# cartridge_pcb.net
KiCad netlist of a schematic drawn in EAGLE
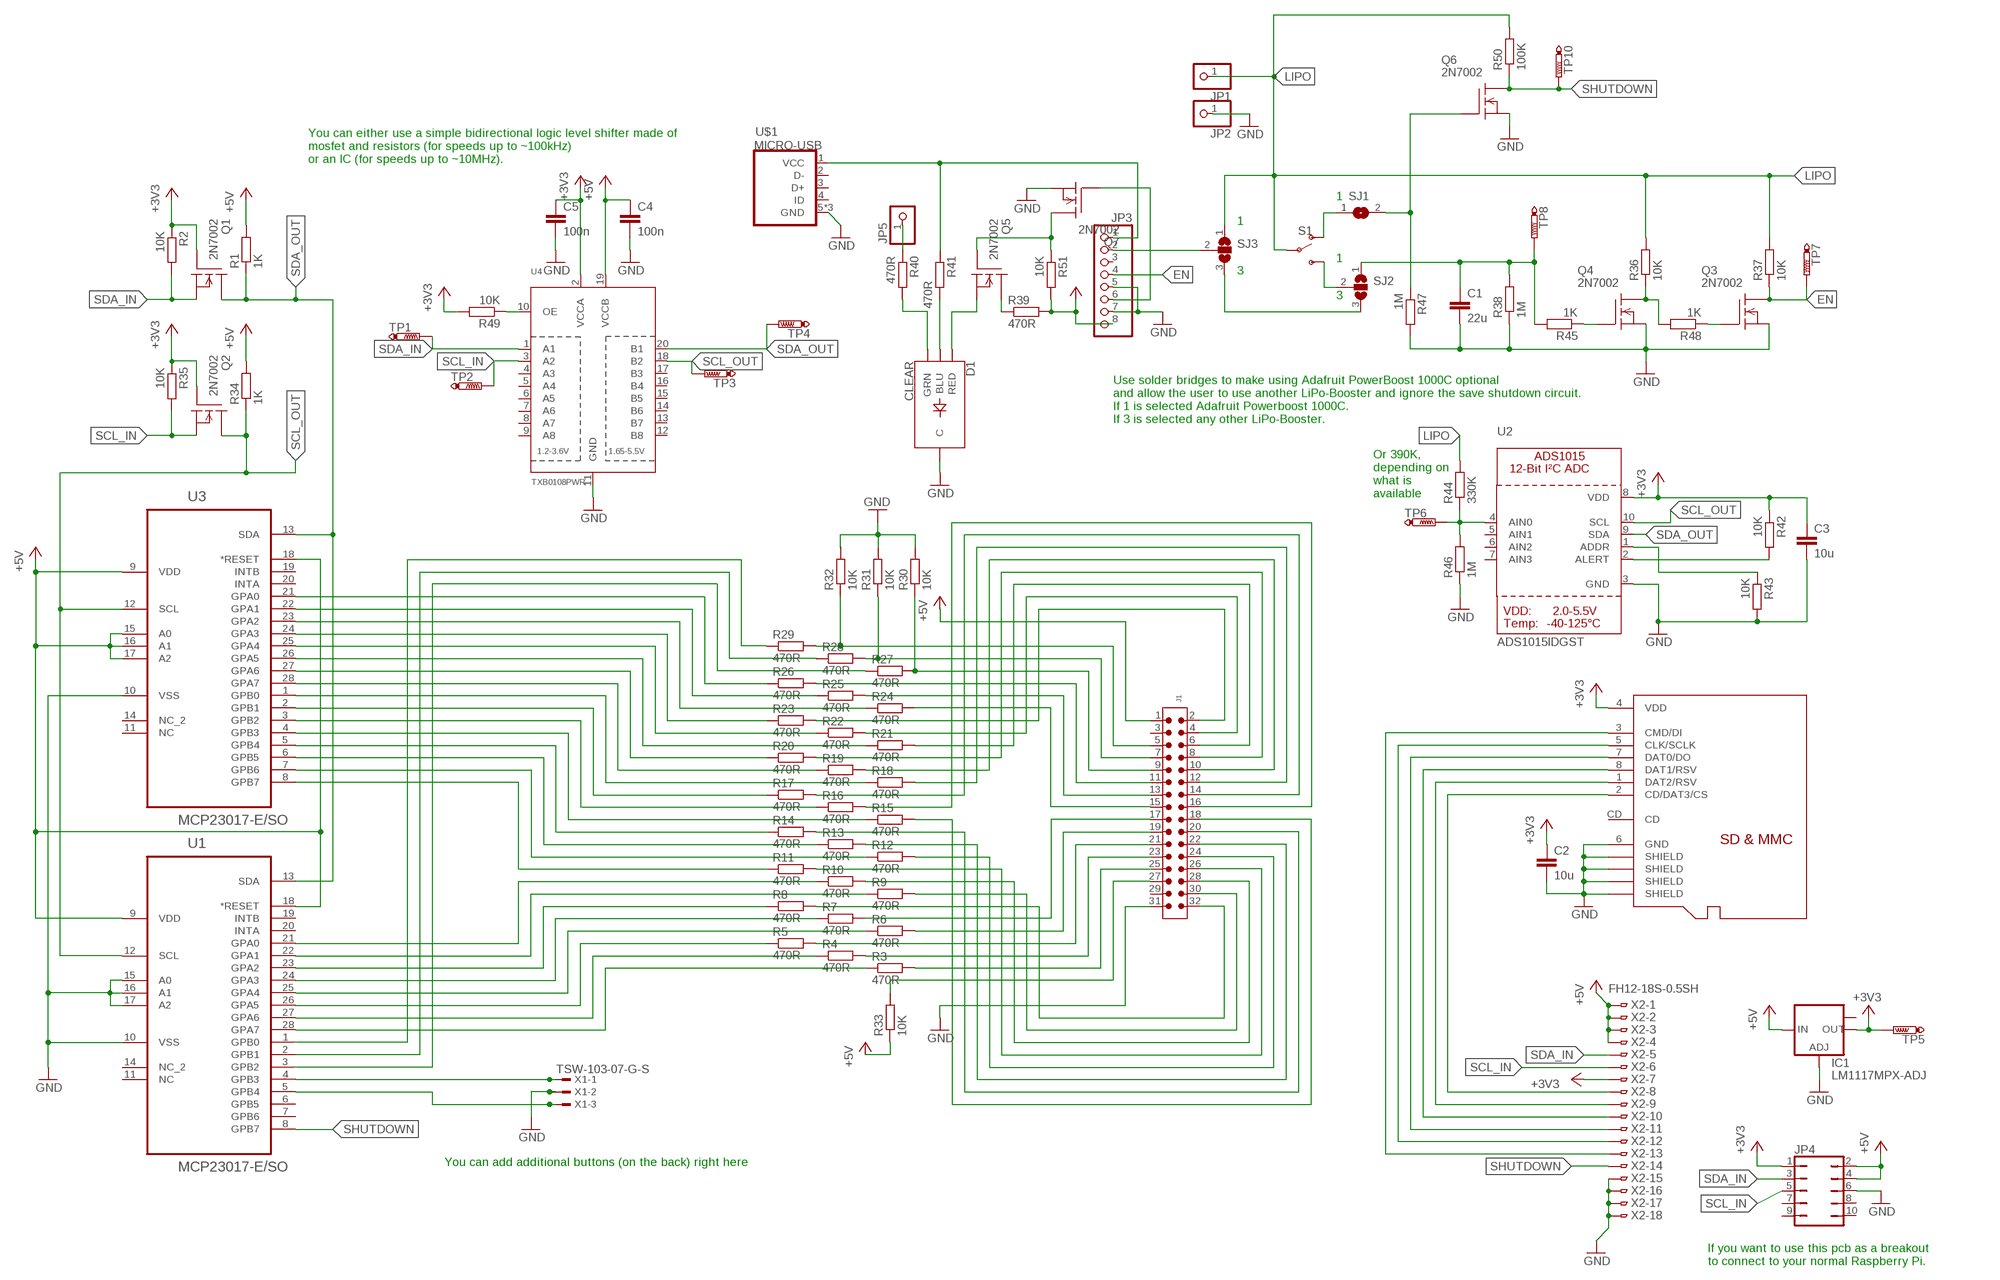
[diagram p0: schematic, sheet 1]

(export (version "E")
  (design (tool "Eeschema 10.0.6"))
  (components
    (comp (ref "C1")
      (value "22u")
      (footprint "eagle-import:C0805")
      (libsource (lib "eagle-import") (part "C-EUC0805"))
    )
    (comp (ref "C2")
      (value "10u")
      (footprint "eagle-import:C0805")
      (libsource (lib "eagle-import") (part "C-EUC0805"))
    )
    (comp (ref "C3")
      (value "10u")
      (footprint "eagle-import:C0805")
      (libsource (lib "eagle-import") (part "C-EUC0805"))
    )
    (comp (ref "C4")
      (value "100n")
      (footprint "eagle-import:C0805")
      (libsource (lib "eagle-import") (part "C-EUC0805"))
    )
    (comp (ref "C5")
      (value "100n")
      (footprint "eagle-import:C0805")
      (libsource (lib "eagle-import") (part "C-EUC0805"))
    )
    (comp (ref "D1")
      (value "CLEAR")
      (footprint "eagle-import:LED-RGB-THRU")
      (libsource (lib "eagle-import") (part "LED-RGB-CCCLEAR"))
    )
    (comp (ref "IC1")
      (value "LM1117MPX-ADJ")
      (footprint "eagle-import:SOT223")
      (libsource (lib "eagle-import") (part "LM1117MPX-ADJ"))
    )
    (comp (ref "J1")
      (value "6130XX21121_61303221121")
      (footprint "eagle-import:61303221121")
      (libsource (lib "eagle-import") (part "6130XX21121_61303221121"))
    )
    (comp (ref "JP1")
      (value "PINHD-1X1")
      (footprint "eagle-import:1X01")
      (libsource (lib "eagle-import") (part "PINHD-1X1"))
    )
    (comp (ref "JP2")
      (value "PINHD-1X1")
      (footprint "eagle-import:1X01")
      (libsource (lib "eagle-import") (part "PINHD-1X1"))
    )
    (comp (ref "JP3")
      (value "HEADER-1X8ROUND")
      (footprint "eagle-import:1X08_ROUND")
      (libsource (lib "eagle-import") (part "HEADER-1X8ROUND"))
    )
    (comp (ref "JP4")
      (value "JP5Q")
      (footprint "eagle-import:JP5Q")
      (libsource (lib "eagle-import") (part "JP5Q"))
    )
    (comp (ref "JP5")
      (value "PINHD-1X1")
      (footprint "eagle-import:1X01")
      (libsource (lib "eagle-import") (part "PINHD-1X1"))
    )
    (comp (ref "Q1")
      (value "2N7002")
      (footprint "eagle-import:SOT23")
      (libsource (lib "eagle-import") (part "2N7002"))
    )
    (comp (ref "Q2")
      (value "2N7002")
      (footprint "eagle-import:SOT23")
      (libsource (lib "eagle-import") (part "2N7002"))
    )
    (comp (ref "Q3")
      (value "2N7002")
      (footprint "eagle-import:SOT23")
      (libsource (lib "eagle-import") (part "2N7002"))
    )
    (comp (ref "Q4")
      (value "2N7002")
      (footprint "eagle-import:SOT23")
      (libsource (lib "eagle-import") (part "2N7002"))
    )
    (comp (ref "Q5")
      (value "2N7002")
      (footprint "eagle-import:SOT23")
      (libsource (lib "eagle-import") (part "2N7002"))
    )
    (comp (ref "Q6")
      (value "2N7002")
      (footprint "eagle-import:SOT23")
      (libsource (lib "eagle-import") (part "2N7002"))
    )
    (comp (ref "Q7")
      (value "2N7002")
      (footprint "eagle-import:SOT23")
      (libsource (lib "eagle-import") (part "2N7002"))
    )
    (comp (ref "R1")
      (value "1K")
      (footprint "eagle-import:R0805")
      (libsource (lib "eagle-import") (part "R-EU_R0805"))
    )
    (comp (ref "R2")
      (value "10K")
      (footprint "eagle-import:R0805")
      (libsource (lib "eagle-import") (part "R-EU_R0805"))
    )
    (comp (ref "R3")
      (value "470R")
      (footprint "eagle-import:R0805")
      (libsource (lib "eagle-import") (part "R-EU_R0805"))
    )
    (comp (ref "R4")
      (value "470R")
      (footprint "eagle-import:R0805")
      (libsource (lib "eagle-import") (part "R-EU_R0805"))
    )
    (comp (ref "R5")
      (value "470R")
      (footprint "eagle-import:R0805")
      (libsource (lib "eagle-import") (part "R-EU_R0805"))
    )
    (comp (ref "R6")
      (value "470R")
      (footprint "eagle-import:R0805")
      (libsource (lib "eagle-import") (part "R-EU_R0805"))
    )
    (comp (ref "R7")
      (value "470R")
      (footprint "eagle-import:R0805")
      (libsource (lib "eagle-import") (part "R-EU_R0805"))
    )
    (comp (ref "R8")
      (value "470R")
      (footprint "eagle-import:R0805")
      (libsource (lib "eagle-import") (part "R-EU_R0805"))
    )
    (comp (ref "R9")
      (value "470R")
      (footprint "eagle-import:R0805")
      (libsource (lib "eagle-import") (part "R-EU_R0805"))
    )
    (comp (ref "R10")
      (value "470R")
      (footprint "eagle-import:R0805")
      (libsource (lib "eagle-import") (part "R-EU_R0805"))
    )
    (comp (ref "R11")
      (value "470R")
      (footprint "eagle-import:R0805")
      (libsource (lib "eagle-import") (part "R-EU_R0805"))
    )
    (comp (ref "R12")
      (value "470R")
      (footprint "eagle-import:R0805")
      (libsource (lib "eagle-import") (part "R-EU_R0805"))
    )
    (comp (ref "R13")
      (value "470R")
      (footprint "eagle-import:R0805")
      (libsource (lib "eagle-import") (part "R-EU_R0805"))
    )
    (comp (ref "R14")
      (value "470R")
      (footprint "eagle-import:R0805")
      (libsource (lib "eagle-import") (part "R-EU_R0805"))
    )
    (comp (ref "R15")
      (value "470R")
      (footprint "eagle-import:R0805")
      (libsource (lib "eagle-import") (part "R-EU_R0805"))
    )
    (comp (ref "R16")
      (value "470R")
      (footprint "eagle-import:R0805")
      (libsource (lib "eagle-import") (part "R-EU_R0805"))
    )
    (comp (ref "R17")
      (value "470R")
      (footprint "eagle-import:R0805")
      (libsource (lib "eagle-import") (part "R-EU_R0805"))
    )
    (comp (ref "R18")
      (value "470R")
      (footprint "eagle-import:R0805")
      (libsource (lib "eagle-import") (part "R-EU_R0805"))
    )
    (comp (ref "R19")
      (value "470R")
      (footprint "eagle-import:R0805")
      (libsource (lib "eagle-import") (part "R-EU_R0805"))
    )
    (comp (ref "R20")
      (value "470R")
      (footprint "eagle-import:R0805")
      (libsource (lib "eagle-import") (part "R-EU_R0805"))
    )
    (comp (ref "R21")
      (value "470R")
      (footprint "eagle-import:R0805")
      (libsource (lib "eagle-import") (part "R-EU_R0805"))
    )
    (comp (ref "R22")
      (value "470R")
      (footprint "eagle-import:R0805")
      (libsource (lib "eagle-import") (part "R-EU_R0805"))
    )
    (comp (ref "R23")
      (value "470R")
      (footprint "eagle-import:R0805")
      (libsource (lib "eagle-import") (part "R-EU_R0805"))
    )
    (comp (ref "R24")
      (value "470R")
      (footprint "eagle-import:R0805")
      (libsource (lib "eagle-import") (part "R-EU_R0805"))
    )
    (comp (ref "R25")
      (value "470R")
      (footprint "eagle-import:R0805")
      (libsource (lib "eagle-import") (part "R-EU_R0805"))
    )
    (comp (ref "R26")
      (value "470R")
      (footprint "eagle-import:R0805")
      (libsource (lib "eagle-import") (part "R-EU_R0805"))
    )
    (comp (ref "R27")
      (value "470R")
      (footprint "eagle-import:R0805")
      (libsource (lib "eagle-import") (part "R-EU_R0805"))
    )
    (comp (ref "R28")
      (value "470R")
      (footprint "eagle-import:R0805")
      (libsource (lib "eagle-import") (part "R-EU_R0805"))
    )
    (comp (ref "R29")
      (value "470R")
      (footprint "eagle-import:R0805")
      (libsource (lib "eagle-import") (part "R-EU_R0805"))
    )
    (comp (ref "R30")
      (value "10K")
      (footprint "eagle-import:R0805")
      (libsource (lib "eagle-import") (part "R-EU_R0805"))
    )
    (comp (ref "R31")
      (value "10K")
      (footprint "eagle-import:R0805")
      (libsource (lib "eagle-import") (part "R-EU_R0805"))
    )
    (comp (ref "R32")
      (value "10K")
      (footprint "eagle-import:R0805")
      (libsource (lib "eagle-import") (part "R-EU_R0805"))
    )
    (comp (ref "R33")
      (value "10K")
      (footprint "eagle-import:R0805")
      (libsource (lib "eagle-import") (part "R-EU_R0805"))
    )
    (comp (ref "R34")
      (value "1K")
      (footprint "eagle-import:R0805")
      (libsource (lib "eagle-import") (part "R-EU_R0805"))
    )
    (comp (ref "R35")
      (value "10K")
      (footprint "eagle-import:R0805")
      (libsource (lib "eagle-import") (part "R-EU_R0805"))
    )
    (comp (ref "R36")
      (value "10K")
      (footprint "eagle-import:R0805")
      (libsource (lib "eagle-import") (part "R-EU_R0805"))
    )
    (comp (ref "R37")
      (value "10K")
      (footprint "eagle-import:R0805")
      (libsource (lib "eagle-import") (part "R-EU_R0805"))
    )
    (comp (ref "R38")
      (value "1M")
      (footprint "eagle-import:R0805")
      (libsource (lib "eagle-import") (part "R-EU_R0805"))
    )
    (comp (ref "R39")
      (value "470R")
      (footprint "eagle-import:R0805")
      (libsource (lib "eagle-import") (part "R-EU_R0805"))
    )
    (comp (ref "R40")
      (value "470R")
      (footprint "eagle-import:R0805")
      (libsource (lib "eagle-import") (part "R-EU_R0805"))
    )
    (comp (ref "R41")
      (value "470R")
      (footprint "eagle-import:R0805")
      (libsource (lib "eagle-import") (part "R-EU_R0805"))
    )
    (comp (ref "R42")
      (value "10K")
      (footprint "eagle-import:R0805")
      (libsource (lib "eagle-import") (part "R-EU_R0805"))
    )
    (comp (ref "R43")
      (value "10K")
      (footprint "eagle-import:R0805")
      (libsource (lib "eagle-import") (part "R-EU_R0805"))
    )
    (comp (ref "R44")
      (value "330K")
      (footprint "eagle-import:R0805")
      (libsource (lib "eagle-import") (part "R-EU_R0805"))
    )
    (comp (ref "R45")
      (value "1K")
      (footprint "eagle-import:R0805")
      (libsource (lib "eagle-import") (part "R-EU_R0805"))
    )
    (comp (ref "R46")
      (value "1M")
      (footprint "eagle-import:R0805")
      (libsource (lib "eagle-import") (part "R-EU_R0805"))
    )
    (comp (ref "R47")
      (value "1M")
      (footprint "eagle-import:R0805")
      (libsource (lib "eagle-import") (part "R-EU_R0805"))
    )
    (comp (ref "R48")
      (value "1K")
      (footprint "eagle-import:R0805")
      (libsource (lib "eagle-import") (part "R-EU_R0805"))
    )
    (comp (ref "R49")
      (value "10K")
      (footprint "eagle-import:R0805")
      (libsource (lib "eagle-import") (part "R-EU_R0805"))
    )
    (comp (ref "R50")
      (value "100K")
      (footprint "eagle-import:R0805")
      (libsource (lib "eagle-import") (part "R-EU_R0805"))
    )
    (comp (ref "R51")
      (value "10K")
      (footprint "eagle-import:R0805")
      (libsource (lib "eagle-import") (part "R-EU_R0805"))
    )
    (comp (ref "S1")
      (value "SWITCH-SPDT-PTH-8.6X4.3MM-LOCK")
      (footprint "eagle-import:SWITCH_SPDT_8.6X4.3MM_LOCK")
      (libsource (lib "eagle-import") (part "SWITCH-SPDT-PTH-8.6X4.3MM-LOCK"))
    )
    (comp (ref "SJ1") (value "SJ") (footprint "eagle-import:SJ") (libsource (lib "eagle-import") (part "SJ")))
    (comp (ref "SJ2")
      (value "SJ2W")
      (footprint "eagle-import:SJ_2")
      (libsource (lib "eagle-import") (part "SJ2W"))
    )
    (comp (ref "SJ3")
      (value "SJ2W")
      (footprint "eagle-import:SJ_2")
      (libsource (lib "eagle-import") (part "SJ2W"))
    )
    (comp (ref "TP1")
      (value "PTR1TP10R")
      (footprint "eagle-import:TP10R")
      (libsource (lib "eagle-import") (part "PTR1TP10R"))
    )
    (comp (ref "TP2")
      (value "PTR1TP10R")
      (footprint "eagle-import:TP10R")
      (libsource (lib "eagle-import") (part "PTR1TP10R"))
    )
    (comp (ref "TP3")
      (value "PTR1TP10R")
      (footprint "eagle-import:TP10R")
      (libsource (lib "eagle-import") (part "PTR1TP10R"))
    )
    (comp (ref "TP4")
      (value "PTR1TP10R")
      (footprint "eagle-import:TP10R")
      (libsource (lib "eagle-import") (part "PTR1TP10R"))
    )
    (comp (ref "TP5")
      (value "PTR1TP10R")
      (footprint "eagle-import:TP10R")
      (libsource (lib "eagle-import") (part "PTR1TP10R"))
    )
    (comp (ref "TP6")
      (value "PTR1TP10R")
      (footprint "eagle-import:TP10R")
      (libsource (lib "eagle-import") (part "PTR1TP10R"))
    )
    (comp (ref "TP7")
      (value "PTR1TP10R")
      (footprint "eagle-import:TP10R")
      (libsource (lib "eagle-import") (part "PTR1TP10R"))
    )
    (comp (ref "TP8")
      (value "PTR1TP10R")
      (footprint "eagle-import:TP10R")
      (libsource (lib "eagle-import") (part "PTR1TP10R"))
    )
    (comp (ref "TP10")
      (value "PTR1TP10R")
      (footprint "eagle-import:TP10R")
      (libsource (lib "eagle-import") (part "PTR1TP10R"))
    )
    (comp (ref "U$1")
      (value "MICRO-USB")
      (footprint "eagle-import:MICRO-USB")
      (libsource (lib "eagle-import") (part "MICRO-USB"))
    )
    (comp (ref "U$2")
      (value "MICROSD")
      (footprint "eagle-import:C12075")
      (libsource (lib "eagle-import") (part "MICROSD"))
    )
    (comp (ref "U1")
      (value "MCP23017-E/SO")
      (footprint "eagle-import:SOIC127P1032X265-28N")
      (libsource (lib "eagle-import") (part "MCP23017-E/SO"))
    )
    (comp (ref "U2")
      (value "ADS1015IDGST")
      (footprint "eagle-import:MSOP10")
      (libsource (lib "eagle-import") (part "ADC_ADS1015"))
    )
    (comp (ref "U3")
      (value "MCP23017-E/SO")
      (footprint "eagle-import:SOIC127P1032X265-28N")
      (libsource (lib "eagle-import") (part "MCP23017-E/SO"))
    )
    (comp (ref "U4")
      (value "TXB0108PWR")
      (footprint "eagle-import:TSSOP20")
      (libsource (lib "eagle-import") (part "TXB0108PWR"))
    )
    (comp (ref "X1")
      (value "TSW-103-07-G-S")
      (footprint "eagle-import:TSW-103-XX-G-S")
      (fields (field (name "MF") "Samtec Inc."))
      (libsource (lib "eagle-import") (part "TSW-103--G-S07"))
    )
    (comp (ref "X2")
      (value "FH12-18S-0.5SH")
      (footprint "eagle-import:FH12-18S-0.5SH")
      (fields (field (name "MPN") "FH12-18S-0.5SH(55)"))
      (libsource (lib "eagle-import") (part "FH12-18S-0.5SH"))
    )
  )
  (nets
    (net (code "1") (name "+3V3") (class "Default")
      (node (ref "C2") (pin "1") (pinfunction "1_1") (pintype "passive"))
      (node (ref "C3") (pin "1") (pinfunction "1_1") (pintype "passive"))
      (node (ref "C5") (pin "1") (pinfunction "1_1") (pintype "passive"))
      (node (ref "IC1") (pin "2") (pinfunction "OUT_2") (pintype "passive"))
      (node (ref "JP4") (pin "1") (pinfunction "1_1") (pintype "passive"))
      (node (ref "Q1") (pin "1") (pinfunction "G_1") (pintype "passive"))
      (node (ref "Q2") (pin "1") (pinfunction "G_1") (pintype "passive"))
      (node (ref "R2") (pin "1") (pinfunction "1_1") (pintype "passive"))
      (node (ref "R35") (pin "1") (pinfunction "1_1") (pintype "passive"))
      (node (ref "R42") (pin "1") (pinfunction "1_1") (pintype "passive"))
      (node (ref "R49") (pin "2") (pinfunction "2_2") (pintype "passive"))
      (node (ref "TP5") (pin "TP") (pinfunction "TP_TP") (pintype "input"))
      (node (ref "U$2") (pin "4") (pinfunction "VDD_4") (pintype "power_in"))
      (node (ref "U2") (pin "8") (pinfunction "VDD_8") (pintype "bidirectional"))
      (node (ref "U4") (pin "2") (pinfunction "VCCA_2") (pintype "bidirectional"))
      (node (ref "X2") (pin "7") (pinfunction "1_7") (pintype "passive"))
    )
    (net (code "2") (name "+5V") (class "Default")
      (node (ref "C4") (pin "1") (pinfunction "1_1") (pintype "passive"))
      (node (ref "IC1") (pin "3") (pinfunction "IN_3") (pintype "input"))
      (node (ref "J1") (pin "1") (pinfunction "1_1") (pintype "passive"))
      (node (ref "JP3") (pin "8") (pinfunction "8_8") (pintype "passive"))
      (node (ref "JP4") (pin "2") (pinfunction "2_2") (pintype "passive"))
      (node (ref "JP4") (pin "4") (pinfunction "4_4") (pintype "passive"))
      (node (ref "R1") (pin "2") (pinfunction "2_2") (pintype "passive"))
      (node (ref "R33") (pin "1") (pinfunction "1_1") (pintype "passive"))
      (node (ref "R34") (pin "2") (pinfunction "2_2") (pintype "passive"))
      (node (ref "R39") (pin "2") (pinfunction "2_2") (pintype "passive"))
      (node (ref "R51") (pin "2") (pinfunction "2_2") (pintype "passive"))
      (node (ref "U1") (pin "18") (pinfunction "*RESET_18") (pintype "output"))
      (node (ref "U1") (pin "9") (pinfunction "VDD_9") (pintype "power_in"))
      (node (ref "U3") (pin "15") (pinfunction "A0_15") (pintype "input"))
      (node (ref "U3") (pin "16") (pinfunction "A1_16") (pintype "input"))
      (node (ref "U3") (pin "17") (pinfunction "A2_17") (pintype "input"))
      (node (ref "U3") (pin "18") (pinfunction "*RESET_18") (pintype "output"))
      (node (ref "U3") (pin "9") (pinfunction "VDD_9") (pintype "power_in"))
      (node (ref "U4") (pin "19") (pinfunction "VCCB_19") (pintype "bidirectional"))
      (node (ref "X2") (pin "1") (pinfunction "1_1") (pintype "passive"))
      (node (ref "X2") (pin "2") (pinfunction "1_2") (pintype "passive"))
      (node (ref "X2") (pin "3") (pinfunction "1_3") (pintype "passive"))
      (node (ref "X2") (pin "4") (pinfunction "1_4") (pintype "passive"))
    )
    (net (code "3") (name "EN") (class "Default")
      (node (ref "JP3") (pin "4") (pinfunction "4_4") (pintype "passive"))
      (node (ref "Q3") (pin "3") (pinfunction "D_3") (pintype "passive"))
      (node (ref "R37") (pin "1") (pinfunction "1_1") (pintype "passive"))
      (node (ref "TP7") (pin "TP") (pinfunction "TP_TP") (pintype "input"))
    )
    (net (code "4") (name "GND") (class "Default")
      (node (ref "C1") (pin "2") (pinfunction "2_2") (pintype "passive"))
      (node (ref "C2") (pin "2") (pinfunction "2_2") (pintype "passive"))
      (node (ref "C3") (pin "2") (pinfunction "2_2") (pintype "passive"))
      (node (ref "C4") (pin "2") (pinfunction "2_2") (pintype "passive"))
      (node (ref "C5") (pin "2") (pinfunction "2_2") (pintype "passive"))
      (node (ref "D1") (pin "2") (pinfunction "C_2") (pintype "bidirectional"))
      (node (ref "IC1") (pin "1") (pinfunction "ADJ_1") (pintype "input"))
      (node (ref "J1") (pin "31") (pinfunction "31_31") (pintype "passive"))
      (node (ref "JP2") (pin "1") (pinfunction "1_1") (pintype "passive"))
      (node (ref "JP3") (pin "5") (pinfunction "5_5") (pintype "passive"))
      (node (ref "JP3") (pin "7") (pinfunction "7_7") (pintype "passive"))
      (node (ref "JP4") (pin "6") (pinfunction "6_6") (pintype "passive"))
      (node (ref "Q3") (pin "2") (pinfunction "S_2") (pintype "passive"))
      (node (ref "Q4") (pin "2") (pinfunction "S_2") (pintype "passive"))
      (node (ref "Q6") (pin "2") (pinfunction "S_2") (pintype "passive"))
      (node (ref "Q7") (pin "2") (pinfunction "S_2") (pintype "passive"))
      (node (ref "R30") (pin "2") (pinfunction "2_2") (pintype "passive"))
      (node (ref "R31") (pin "2") (pinfunction "2_2") (pintype "passive"))
      (node (ref "R32") (pin "2") (pinfunction "2_2") (pintype "passive"))
      (node (ref "R38") (pin "1") (pinfunction "1_1") (pintype "passive"))
      (node (ref "R43") (pin "2") (pinfunction "2_2") (pintype "passive"))
      (node (ref "R46") (pin "1") (pinfunction "1_1") (pintype "passive"))
      (node (ref "R47") (pin "2") (pinfunction "2_2") (pintype "passive"))
      (node (ref "U$1") (pin "5") (pinfunction "GND_5") (pintype "power_in"))
      (node (ref "U$1") (pin "GND1") (pinfunction "GND_GND1") (pintype "power_in"))
      (node (ref "U$1") (pin "GND2") (pinfunction "GND_GND2") (pintype "power_in"))
      (node (ref "U$2") (pin "6") (pinfunction "GND_6") (pintype "power_in"))
      (node (ref "U$2") (pin "GND@1") (pinfunction "SHIELD_GND@1") (pintype "power_in"))
      (node (ref "U$2") (pin "GND@2") (pinfunction "SHIELD_GND@2") (pintype "power_in"))
      (node (ref "U$2") (pin "GND@3") (pinfunction "SHIELD_GND@3") (pintype "power_in"))
      (node (ref "U$2") (pin "GND@4") (pinfunction "SHIELD_GND@4") (pintype "power_in"))
      (node (ref "U1") (pin "10") (pinfunction "VSS_10") (pintype "power_in"))
      (node (ref "U1") (pin "15") (pinfunction "A0_15") (pintype "input"))
      (node (ref "U1") (pin "16") (pinfunction "A1_16") (pintype "input"))
      (node (ref "U1") (pin "17") (pinfunction "A2_17") (pintype "input"))
      (node (ref "U2") (pin "3") (pinfunction "GND_3") (pintype "bidirectional"))
      (node (ref "U3") (pin "10") (pinfunction "VSS_10") (pintype "power_in"))
      (node (ref "U4") (pin "11") (pinfunction "GND_11") (pintype "bidirectional"))
      (node (ref "X1") (pin "2") (pinfunction "1_2") (pintype "passive"))
      (node (ref "X2") (pin "15") (pinfunction "1_15") (pintype "passive"))
      (node (ref "X2") (pin "16") (pinfunction "1_16") (pintype "passive"))
      (node (ref "X2") (pin "17") (pinfunction "1_17") (pintype "passive"))
      (node (ref "X2") (pin "18") (pinfunction "1_18") (pintype "passive"))
    )
    (net (code "5") (name "LIPO") (class "Default")
      (node (ref "JP1") (pin "1") (pinfunction "1_1") (pintype "passive"))
      (node (ref "R36") (pin "2") (pinfunction "2_2") (pintype "passive"))
      (node (ref "R37") (pin "2") (pinfunction "2_2") (pintype "passive"))
      (node (ref "R44") (pin "2") (pinfunction "2_2") (pintype "passive"))
      (node (ref "R50") (pin "2") (pinfunction "2_2") (pintype "passive"))
      (node (ref "S1") (pin "2") (pinfunction "P_2") (pintype "passive"))
      (node (ref "SJ3") (pin "1") (pinfunction "1_1") (pintype "passive"))
    )
    (net (code "6") (name "Net-(C1-Pad1)") (class "Default")
      (node (ref "C1") (pin "1") (pinfunction "1_1") (pintype "passive"))
      (node (ref "R38") (pin "2") (pinfunction "2_2") (pintype "passive"))
      (node (ref "R45") (pin "2") (pinfunction "2_2") (pintype "passive"))
      (node (ref "SJ2") (pin "1") (pinfunction "1_1") (pintype "passive"))
      (node (ref "TP8") (pin "TP") (pinfunction "TP_TP") (pintype "input"))
    )
    (net (code "7") (name "Net-(D1-BLU)") (class "Default")
      (node (ref "D1") (pin "4") (pinfunction "BLU_4") (pintype "bidirectional"))
      (node (ref "R41") (pin "2") (pinfunction "2_2") (pintype "passive"))
    )
    (net (code "8") (name "Net-(D1-GRN)") (class "Default")
      (node (ref "D1") (pin "3") (pinfunction "GRN_3") (pintype "bidirectional"))
      (node (ref "R40") (pin "2") (pinfunction "2_2") (pintype "passive"))
    )
    (net (code "9") (name "Net-(D1-RED)") (class "Default")
      (node (ref "D1") (pin "1") (pinfunction "RED_1") (pintype "bidirectional"))
      (node (ref "Q5") (pin "2") (pinfunction "S_2") (pintype "passive"))
    )
    (net (code "10") (name "Net-(J1-Pad2)") (class "Default")
      (node (ref "J1") (pin "2") (pinfunction "2_2") (pintype "passive"))
      (node (ref "R23") (pin "2") (pinfunction "2_2") (pintype "passive"))
    )
    (net (code "11") (name "Net-(J1-Pad4)") (class "Default")
      (node (ref "J1") (pin "4") (pinfunction "4_4") (pintype "passive"))
      (node (ref "R22") (pin "2") (pinfunction "2_2") (pintype "passive"))
    )
    (net (code "12") (name "Net-(J1-Pad5)") (class "Default")
      (node (ref "J1") (pin "5") (pinfunction "5_5") (pintype "passive"))
      (node (ref "R29") (pin "2") (pinfunction "2_2") (pintype "passive"))
      (node (ref "R32") (pin "1") (pinfunction "1_1") (pintype "passive"))
    )
    (net (code "13") (name "Net-(J1-Pad6)") (class "Default")
      (node (ref "J1") (pin "6") (pinfunction "6_6") (pintype "passive"))
      (node (ref "R21") (pin "2") (pinfunction "2_2") (pintype "passive"))
    )
    (net (code "14") (name "Net-(J1-Pad7)") (class "Default")
      (node (ref "J1") (pin "7") (pinfunction "7_7") (pintype "passive"))
      (node (ref "R28") (pin "2") (pinfunction "2_2") (pintype "passive"))
      (node (ref "R31") (pin "1") (pinfunction "1_1") (pintype "passive"))
    )
    (net (code "15") (name "Net-(J1-Pad8)") (class "Default")
      (node (ref "J1") (pin "8") (pinfunction "8_8") (pintype "passive"))
      (node (ref "R20") (pin "2") (pinfunction "2_2") (pintype "passive"))
    )
    (net (code "16") (name "Net-(J1-Pad9)") (class "Default")
      (node (ref "J1") (pin "9") (pinfunction "9_9") (pintype "passive"))
      (node (ref "R27") (pin "2") (pinfunction "2_2") (pintype "passive"))
      (node (ref "R30") (pin "1") (pinfunction "1_1") (pintype "passive"))
    )
    (net (code "17") (name "Net-(J1-Pad10)") (class "Default")
      (node (ref "J1") (pin "10") (pinfunction "10_10") (pintype "passive"))
      (node (ref "R19") (pin "2") (pinfunction "2_2") (pintype "passive"))
    )
    (net (code "18") (name "Net-(J1-Pad11)") (class "Default")
      (node (ref "J1") (pin "11") (pinfunction "11_11") (pintype "passive"))
      (node (ref "R26") (pin "2") (pinfunction "2_2") (pintype "passive"))
    )
    (net (code "19") (name "Net-(J1-Pad12)") (class "Default")
      (node (ref "J1") (pin "12") (pinfunction "12_12") (pintype "passive"))
      (node (ref "R18") (pin "2") (pinfunction "2_2") (pintype "passive"))
    )
    (net (code "20") (name "Net-(J1-Pad13)") (class "Default")
      (node (ref "J1") (pin "13") (pinfunction "13_13") (pintype "passive"))
      (node (ref "R25") (pin "2") (pinfunction "2_2") (pintype "passive"))
    )
    (net (code "21") (name "Net-(J1-Pad14)") (class "Default")
      (node (ref "J1") (pin "14") (pinfunction "14_14") (pintype "passive"))
      (node (ref "R17") (pin "2") (pinfunction "2_2") (pintype "passive"))
    )
    (net (code "22") (name "Net-(J1-Pad15)") (class "Default")
      (node (ref "J1") (pin "15") (pinfunction "15_15") (pintype "passive"))
      (node (ref "R24") (pin "2") (pinfunction "2_2") (pintype "passive"))
    )
    (net (code "23") (name "Net-(J1-Pad16)") (class "Default")
      (node (ref "J1") (pin "16") (pinfunction "16_16") (pintype "passive"))
      (node (ref "R16") (pin "2") (pinfunction "2_2") (pintype "passive"))
    )
    (net (code "24") (name "Net-(J1-Pad17)") (class "Default")
      (node (ref "J1") (pin "17") (pinfunction "17_17") (pintype "passive"))
      (node (ref "R7") (pin "2") (pinfunction "2_2") (pintype "passive"))
    )
    (net (code "25") (name "Net-(J1-Pad18)") (class "Default")
      (node (ref "J1") (pin "18") (pinfunction "18_18") (pintype "passive"))
      (node (ref "R15") (pin "2") (pinfunction "2_2") (pintype "passive"))
    )
    (net (code "26") (name "Net-(J1-Pad19)") (class "Default")
      (node (ref "J1") (pin "19") (pinfunction "19_19") (pintype "passive"))
      (node (ref "R6") (pin "2") (pinfunction "2_2") (pintype "passive"))
    )
    (net (code "27") (name "Net-(J1-Pad20)") (class "Default")
      (node (ref "J1") (pin "20") (pinfunction "20_20") (pintype "passive"))
      (node (ref "R14") (pin "2") (pinfunction "2_2") (pintype "passive"))
    )
    (net (code "28") (name "Net-(J1-Pad21)") (class "Default")
      (node (ref "J1") (pin "21") (pinfunction "21_21") (pintype "passive"))
      (node (ref "R5") (pin "2") (pinfunction "2_2") (pintype "passive"))
    )
    (net (code "29") (name "Net-(J1-Pad22)") (class "Default")
      (node (ref "J1") (pin "22") (pinfunction "22_22") (pintype "passive"))
      (node (ref "R13") (pin "2") (pinfunction "2_2") (pintype "passive"))
    )
    (net (code "30") (name "Net-(J1-Pad23)") (class "Default")
      (node (ref "J1") (pin "23") (pinfunction "23_23") (pintype "passive"))
      (node (ref "R4") (pin "2") (pinfunction "2_2") (pintype "passive"))
    )
    (net (code "31") (name "Net-(J1-Pad24)") (class "Default")
      (node (ref "J1") (pin "24") (pinfunction "24_24") (pintype "passive"))
      (node (ref "R12") (pin "2") (pinfunction "2_2") (pintype "passive"))
    )
    (net (code "32") (name "Net-(J1-Pad25)") (class "Default")
      (node (ref "J1") (pin "25") (pinfunction "25_25") (pintype "passive"))
      (node (ref "R3") (pin "2") (pinfunction "2_2") (pintype "passive"))
    )
    (net (code "33") (name "Net-(J1-Pad26)") (class "Default")
      (node (ref "J1") (pin "26") (pinfunction "26_26") (pintype "passive"))
      (node (ref "R11") (pin "2") (pinfunction "2_2") (pintype "passive"))
    )
    (net (code "34") (name "Net-(J1-Pad27)") (class "Default")
      (node (ref "J1") (pin "27") (pinfunction "27_27") (pintype "passive"))
      (node (ref "R33") (pin "2") (pinfunction "2_2") (pintype "passive"))
    )
    (net (code "35") (name "Net-(J1-Pad28)") (class "Default")
      (node (ref "J1") (pin "28") (pinfunction "28_28") (pintype "passive"))
      (node (ref "R10") (pin "2") (pinfunction "2_2") (pintype "passive"))
    )
    (net (code "36") (name "Net-(J1-Pad30)") (class "Default")
      (node (ref "J1") (pin "30") (pinfunction "30_30") (pintype "passive"))
      (node (ref "R9") (pin "2") (pinfunction "2_2") (pintype "passive"))
    )
    (net (code "37") (name "Net-(J1-Pad32)") (class "Default")
      (node (ref "J1") (pin "32") (pinfunction "32_32") (pintype "passive"))
      (node (ref "R8") (pin "2") (pinfunction "2_2") (pintype "passive"))
    )
    (net (code "38") (name "Net-(JP3-Pad2)") (class "Default")
      (node (ref "JP3") (pin "2") (pinfunction "2_2") (pintype "passive"))
      (node (ref "SJ3") (pin "2") (pinfunction "2_2") (pintype "passive"))
    )
    (net (code "39") (name "Net-(JP5-Pad1)") (class "Default")
      (node (ref "JP5") (pin "1") (pinfunction "1_1") (pintype "passive"))
      (node (ref "R40") (pin "1") (pinfunction "1_1") (pintype "passive"))
    )
    (net (code "40") (name "Net-(Q3-G)") (class "Default")
      (node (ref "Q3") (pin "1") (pinfunction "G_1") (pintype "passive"))
      (node (ref "R48") (pin "1") (pinfunction "1_1") (pintype "passive"))
    )
    (net (code "41") (name "Net-(Q4-D)") (class "Default")
      (node (ref "Q4") (pin "3") (pinfunction "D_3") (pintype "passive"))
      (node (ref "R36") (pin "1") (pinfunction "1_1") (pintype "passive"))
      (node (ref "R48") (pin "2") (pinfunction "2_2") (pintype "passive"))
    )
    (net (code "42") (name "Net-(Q4-G)") (class "Default")
      (node (ref "Q4") (pin "1") (pinfunction "G_1") (pintype "passive"))
      (node (ref "R45") (pin "1") (pinfunction "1_1") (pintype "passive"))
    )
    (net (code "43") (name "Net-(Q5-D)") (class "Default")
      (node (ref "Q5") (pin "3") (pinfunction "D_3") (pintype "passive"))
      (node (ref "R39") (pin "1") (pinfunction "1_1") (pintype "passive"))
    )
    (net (code "44") (name "Net-(Q5-G)") (class "Default")
      (node (ref "Q5") (pin "1") (pinfunction "G_1") (pintype "passive"))
      (node (ref "Q7") (pin "3") (pinfunction "D_3") (pintype "passive"))
      (node (ref "R51") (pin "1") (pinfunction "1_1") (pintype "passive"))
    )
    (net (code "45") (name "Net-(Q6-G)") (class "Default")
      (node (ref "Q6") (pin "1") (pinfunction "G_1") (pintype "passive"))
      (node (ref "R47") (pin "1") (pinfunction "1_1") (pintype "passive"))
      (node (ref "SJ1") (pin "2") (pinfunction "2_2") (pintype "passive"))
    )
    (net (code "46") (name "Net-(Q7-G)") (class "Default")
      (node (ref "JP3") (pin "6") (pinfunction "6_6") (pintype "passive"))
      (node (ref "Q7") (pin "1") (pinfunction "G_1") (pintype "passive"))
    )
    (net (code "47") (name "Net-(S1-O)") (class "Default")
      (node (ref "S1") (pin "1") (pinfunction "O_1") (pintype "passive"))
      (node (ref "SJ1") (pin "1") (pinfunction "1_1") (pintype "passive"))
    )
    (net (code "48") (name "Net-(S1-S)") (class "Default")
      (node (ref "S1") (pin "3") (pinfunction "S_3") (pintype "passive"))
      (node (ref "SJ2") (pin "2") (pinfunction "2_2") (pintype "passive"))
    )
    (net (code "49") (name "Net-(SJ2-Pad3)") (class "Default")
      (node (ref "SJ2") (pin "3") (pinfunction "3_3") (pintype "passive"))
      (node (ref "SJ3") (pin "3") (pinfunction "3_3") (pintype "passive"))
    )
    (net (code "50") (name "Net-(U$1-VCC)") (class "Default")
      (node (ref "JP3") (pin "1") (pinfunction "1_1") (pintype "passive"))
      (node (ref "R41") (pin "1") (pinfunction "1_1") (pintype "passive"))
      (node (ref "U$1") (pin "1") (pinfunction "VCC_1") (pintype "power_in"))
    )
    (net (code "51") (name "Net-(U$2-CD{slash}DAT3{slash}CS)") (class "Default")
      (node (ref "U$2") (pin "2") (pinfunction "CD/DAT3/CS_2") (pintype "bidirectional"))
      (node (ref "X2") (pin "8") (pinfunction "1_8") (pintype "passive"))
    )
    (net (code "52") (name "Net-(U$2-CLK{slash}SCLK)") (class "Default")
      (node (ref "U$2") (pin "5") (pinfunction "CLK/SCLK_5") (pintype "bidirectional"))
      (node (ref "X2") (pin "12") (pinfunction "1_12") (pintype "passive"))
    )
    (net (code "53") (name "Net-(U$2-CMD{slash}DI)") (class "Default")
      (node (ref "U$2") (pin "3") (pinfunction "CMD/DI_3") (pintype "bidirectional"))
      (node (ref "X2") (pin "13") (pinfunction "1_13") (pintype "passive"))
    )
    (net (code "54") (name "Net-(U$2-DAT0{slash}DO)") (class "Default")
      (node (ref "U$2") (pin "7") (pinfunction "DAT0/DO_7") (pintype "bidirectional"))
      (node (ref "X2") (pin "11") (pinfunction "1_11") (pintype "passive"))
    )
    (net (code "55") (name "Net-(U$2-DAT1{slash}RSV)") (class "Default")
      (node (ref "U$2") (pin "8") (pinfunction "DAT1/RSV_8") (pintype "bidirectional"))
      (node (ref "X2") (pin "10") (pinfunction "1_10") (pintype "passive"))
    )
    (net (code "56") (name "Net-(U$2-DAT2{slash}RSV)") (class "Default")
      (node (ref "U$2") (pin "1") (pinfunction "DAT2/RSV_1") (pintype "bidirectional"))
      (node (ref "X2") (pin "9") (pinfunction "1_9") (pintype "passive"))
    )
    (net (code "57") (name "Net-(U1-GPA0)") (class "Default")
      (node (ref "R10") (pin "1") (pinfunction "1_1") (pintype "passive"))
      (node (ref "U1") (pin "21") (pinfunction "GPA0_21") (pintype "bidirectional"))
    )
    (net (code "58") (name "Net-(U1-GPA1)") (class "Default")
      (node (ref "R9") (pin "1") (pinfunction "1_1") (pintype "passive"))
      (node (ref "U1") (pin "22") (pinfunction "GPA1_22") (pintype "bidirectional"))
    )
    (net (code "59") (name "Net-(U1-GPA2)") (class "Default")
      (node (ref "R8") (pin "1") (pinfunction "1_1") (pintype "passive"))
      (node (ref "U1") (pin "23") (pinfunction "GPA2_23") (pintype "bidirectional"))
    )
    (net (code "60") (name "Net-(U1-GPA3)") (class "Default")
      (node (ref "R7") (pin "1") (pinfunction "1_1") (pintype "passive"))
      (node (ref "U1") (pin "24") (pinfunction "GPA3_24") (pintype "bidirectional"))
    )
    (net (code "61") (name "Net-(U1-GPA4)") (class "Default")
      (node (ref "R6") (pin "1") (pinfunction "1_1") (pintype "passive"))
      (node (ref "U1") (pin "25") (pinfunction "GPA4_25") (pintype "bidirectional"))
    )
    (net (code "62") (name "Net-(U1-GPA5)") (class "Default")
      (node (ref "R5") (pin "1") (pinfunction "1_1") (pintype "passive"))
      (node (ref "U1") (pin "26") (pinfunction "GPA5_26") (pintype "bidirectional"))
    )
    (net (code "63") (name "Net-(U1-GPA6)") (class "Default")
      (node (ref "R4") (pin "1") (pinfunction "1_1") (pintype "passive"))
      (node (ref "U1") (pin "27") (pinfunction "GPA6_27") (pintype "bidirectional"))
    )
    (net (code "64") (name "Net-(U1-GPA7)") (class "Default")
      (node (ref "R3") (pin "1") (pinfunction "1_1") (pintype "passive"))
      (node (ref "U1") (pin "28") (pinfunction "GPA7_28") (pintype "bidirectional"))
    )
    (net (code "65") (name "Net-(U1-GPB0)") (class "Default")
      (node (ref "R29") (pin "1") (pinfunction "1_1") (pintype "passive"))
      (node (ref "U1") (pin "1") (pinfunction "GPB0_1") (pintype "bidirectional"))
    )
    (net (code "66") (name "Net-(U1-GPB1)") (class "Default")
      (node (ref "R28") (pin "1") (pinfunction "1_1") (pintype "passive"))
      (node (ref "U1") (pin "2") (pinfunction "GPB1_2") (pintype "bidirectional"))
    )
    (net (code "67") (name "Net-(U1-GPB2)") (class "Default")
      (node (ref "R27") (pin "1") (pinfunction "1_1") (pintype "passive"))
      (node (ref "U1") (pin "3") (pinfunction "GPB2_3") (pintype "bidirectional"))
    )
    (net (code "68") (name "Net-(U1-GPB3)") (class "Default")
      (node (ref "U1") (pin "4") (pinfunction "GPB3_4") (pintype "bidirectional"))
      (node (ref "X1") (pin "1") (pinfunction "1_1") (pintype "passive"))
    )
    (net (code "69") (name "Net-(U1-GPB4)") (class "Default")
      (node (ref "U1") (pin "5") (pinfunction "GPB4_5") (pintype "bidirectional"))
      (node (ref "X1") (pin "3") (pinfunction "1_3") (pintype "passive"))
    )
    (net (code "70") (name "Net-(U2-ADDR)") (class "Default")
      (node (ref "R43") (pin "1") (pinfunction "1_1") (pintype "passive"))
      (node (ref "U2") (pin "1") (pinfunction "ADDR_1") (pintype "bidirectional"))
    )
    (net (code "71") (name "Net-(U2-AIN0)") (class "Default")
      (node (ref "R44") (pin "1") (pinfunction "1_1") (pintype "passive"))
      (node (ref "R46") (pin "2") (pinfunction "2_2") (pintype "passive"))
      (node (ref "TP6") (pin "TP") (pinfunction "TP_TP") (pintype "input"))
      (node (ref "U2") (pin "4") (pinfunction "AIN0_4") (pintype "bidirectional"))
    )
    (net (code "72") (name "Net-(U2-ALERT)") (class "Default")
      (node (ref "R42") (pin "2") (pinfunction "2_2") (pintype "passive"))
      (node (ref "U2") (pin "2") (pinfunction "ALERT_2") (pintype "bidirectional"))
    )
    (net (code "73") (name "Net-(U3-GPA0)") (class "Default")
      (node (ref "R26") (pin "1") (pinfunction "1_1") (pintype "passive"))
      (node (ref "U3") (pin "21") (pinfunction "GPA0_21") (pintype "bidirectional"))
    )
    (net (code "74") (name "Net-(U3-GPA1)") (class "Default")
      (node (ref "R25") (pin "1") (pinfunction "1_1") (pintype "passive"))
      (node (ref "U3") (pin "22") (pinfunction "GPA1_22") (pintype "bidirectional"))
    )
    (net (code "75") (name "Net-(U3-GPA2)") (class "Default")
      (node (ref "R24") (pin "1") (pinfunction "1_1") (pintype "passive"))
      (node (ref "U3") (pin "23") (pinfunction "GPA2_23") (pintype "bidirectional"))
    )
    (net (code "76") (name "Net-(U3-GPA3)") (class "Default")
      (node (ref "R23") (pin "1") (pinfunction "1_1") (pintype "passive"))
      (node (ref "U3") (pin "24") (pinfunction "GPA3_24") (pintype "bidirectional"))
    )
    (net (code "77") (name "Net-(U3-GPA4)") (class "Default")
      (node (ref "R22") (pin "1") (pinfunction "1_1") (pintype "passive"))
      (node (ref "U3") (pin "25") (pinfunction "GPA4_25") (pintype "bidirectional"))
    )
    (net (code "78") (name "Net-(U3-GPA5)") (class "Default")
      (node (ref "R21") (pin "1") (pinfunction "1_1") (pintype "passive"))
      (node (ref "U3") (pin "26") (pinfunction "GPA5_26") (pintype "bidirectional"))
    )
    (net (code "79") (name "Net-(U3-GPA6)") (class "Default")
      (node (ref "R20") (pin "1") (pinfunction "1_1") (pintype "passive"))
      (node (ref "U3") (pin "27") (pinfunction "GPA6_27") (pintype "bidirectional"))
    )
    (net (code "80") (name "Net-(U3-GPA7)") (class "Default")
      (node (ref "R19") (pin "1") (pinfunction "1_1") (pintype "passive"))
      (node (ref "U3") (pin "28") (pinfunction "GPA7_28") (pintype "bidirectional"))
    )
    (net (code "81") (name "Net-(U3-GPB0)") (class "Default")
      (node (ref "R18") (pin "1") (pinfunction "1_1") (pintype "passive"))
      (node (ref "U3") (pin "1") (pinfunction "GPB0_1") (pintype "bidirectional"))
    )
    (net (code "82") (name "Net-(U3-GPB1)") (class "Default")
      (node (ref "R17") (pin "1") (pinfunction "1_1") (pintype "passive"))
      (node (ref "U3") (pin "2") (pinfunction "GPB1_2") (pintype "bidirectional"))
    )
    (net (code "83") (name "Net-(U3-GPB2)") (class "Default")
      (node (ref "R16") (pin "1") (pinfunction "1_1") (pintype "passive"))
      (node (ref "U3") (pin "3") (pinfunction "GPB2_3") (pintype "bidirectional"))
    )
    (net (code "84") (name "Net-(U3-GPB3)") (class "Default")
      (node (ref "R15") (pin "1") (pinfunction "1_1") (pintype "passive"))
      (node (ref "U3") (pin "4") (pinfunction "GPB3_4") (pintype "bidirectional"))
    )
    (net (code "85") (name "Net-(U3-GPB4)") (class "Default")
      (node (ref "R14") (pin "1") (pinfunction "1_1") (pintype "passive"))
      (node (ref "U3") (pin "5") (pinfunction "GPB4_5") (pintype "bidirectional"))
    )
    (net (code "86") (name "Net-(U3-GPB5)") (class "Default")
      (node (ref "R13") (pin "1") (pinfunction "1_1") (pintype "passive"))
      (node (ref "U3") (pin "6") (pinfunction "GPB5_6") (pintype "bidirectional"))
    )
    (net (code "87") (name "Net-(U3-GPB6)") (class "Default")
      (node (ref "R12") (pin "1") (pinfunction "1_1") (pintype "passive"))
      (node (ref "U3") (pin "7") (pinfunction "GPB6_7") (pintype "bidirectional"))
    )
    (net (code "88") (name "Net-(U3-GPB7)") (class "Default")
      (node (ref "R11") (pin "1") (pinfunction "1_1") (pintype "passive"))
      (node (ref "U3") (pin "8") (pinfunction "GPB7_8") (pintype "bidirectional"))
    )
    (net (code "89") (name "Net-(U4-OE)") (class "Default")
      (node (ref "R49") (pin "1") (pinfunction "1_1") (pintype "passive"))
      (node (ref "U4") (pin "10") (pinfunction "OE_10") (pintype "bidirectional"))
    )
    (net (code "90") (name "SCL_IN") (class "Default")
      (node (ref "JP4") (pin "5") (pinfunction "5_5") (pintype "passive"))
      (node (ref "Q2") (pin "2") (pinfunction "S_2") (pintype "passive"))
      (node (ref "R35") (pin "2") (pinfunction "2_2") (pintype "passive"))
      (node (ref "TP2") (pin "TP") (pinfunction "TP_TP") (pintype "input"))
      (node (ref "U4") (pin "3") (pinfunction "A2_3") (pintype "bidirectional"))
      (node (ref "X2") (pin "6") (pinfunction "1_6") (pintype "passive"))
    )
    (net (code "91") (name "SCL_OUT") (class "Default")
      (node (ref "Q2") (pin "3") (pinfunction "D_3") (pintype "passive"))
      (node (ref "R34") (pin "1") (pinfunction "1_1") (pintype "passive"))
      (node (ref "TP3") (pin "TP") (pinfunction "TP_TP") (pintype "input"))
      (node (ref "U1") (pin "12") (pinfunction "SCL_12") (pintype "input"))
      (node (ref "U2") (pin "10") (pinfunction "SCL_10") (pintype "bidirectional"))
      (node (ref "U3") (pin "12") (pinfunction "SCL_12") (pintype "input"))
      (node (ref "U4") (pin "18") (pinfunction "B2_18") (pintype "bidirectional"))
    )
    (net (code "92") (name "SDA_IN") (class "Default")
      (node (ref "JP4") (pin "3") (pinfunction "3_3") (pintype "passive"))
      (node (ref "Q1") (pin "2") (pinfunction "S_2") (pintype "passive"))
      (node (ref "R2") (pin "2") (pinfunction "2_2") (pintype "passive"))
      (node (ref "TP1") (pin "TP") (pinfunction "TP_TP") (pintype "input"))
      (node (ref "U4") (pin "1") (pinfunction "A1_1") (pintype "bidirectional"))
      (node (ref "X2") (pin "5") (pinfunction "1_5") (pintype "passive"))
    )
    (net (code "93") (name "SDA_OUT") (class "Default")
      (node (ref "Q1") (pin "3") (pinfunction "D_3") (pintype "passive"))
      (node (ref "R1") (pin "1") (pinfunction "1_1") (pintype "passive"))
      (node (ref "TP4") (pin "TP") (pinfunction "TP_TP") (pintype "input"))
      (node (ref "U1") (pin "13") (pinfunction "SDA_13") (pintype "bidirectional"))
      (node (ref "U2") (pin "9") (pinfunction "SDA_9") (pintype "bidirectional"))
      (node (ref "U3") (pin "13") (pinfunction "SDA_13") (pintype "bidirectional"))
      (node (ref "U4") (pin "20") (pinfunction "B1_20") (pintype "bidirectional"))
    )
    (net (code "94") (name "SHUTDOWN") (class "Default")
      (node (ref "Q6") (pin "3") (pinfunction "D_3") (pintype "passive"))
      (node (ref "R50") (pin "1") (pinfunction "1_1") (pintype "passive"))
      (node (ref "TP10") (pin "TP") (pinfunction "TP_TP") (pintype "input"))
      (node (ref "U1") (pin "8") (pinfunction "GPB7_8") (pintype "bidirectional"))
      (node (ref "X2") (pin "14") (pinfunction "1_14") (pintype "passive"))
    )
    (net (code "95") (name "unconnected-(IC1-OUT1-PadTAB)") (class "Default")
      (node (ref "IC1") (pin "TAB") (pinfunction "OUT1_TAB") (pintype "passive"))
    )
    (net (code "96") (name "unconnected-(J1-Pad3)") (class "Default")
      (node (ref "J1") (pin "3") (pinfunction "3_3") (pintype "passive"))
    )
    (net (code "97") (name "unconnected-(J1-Pad29)") (class "Default")
      (node (ref "J1") (pin "29") (pinfunction "29_29") (pintype "passive"))
    )
    (net (code "98") (name "unconnected-(JP3-Pad3)") (class "Default")
      (node (ref "JP3") (pin "3") (pinfunction "3_3") (pintype "passive"))
    )
    (net (code "99") (name "unconnected-(JP4-Pad7)") (class "Default")
      (node (ref "JP4") (pin "7") (pinfunction "7_7") (pintype "passive"))
    )
    (net (code "100") (name "unconnected-(JP4-Pad8)") (class "Default")
      (node (ref "JP4") (pin "8") (pinfunction "8_8") (pintype "passive"))
    )
    (net (code "101") (name "unconnected-(JP4-Pad9)") (class "Default")
      (node (ref "JP4") (pin "9") (pinfunction "9_9") (pintype "passive"))
    )
    (net (code "102") (name "unconnected-(JP4-Pad10)") (class "Default")
      (node (ref "JP4") (pin "10") (pinfunction "10_10") (pintype "passive"))
    )
    (net (code "103") (name "unconnected-(U$1-D+-Pad3)") (class "Default")
      (node (ref "U$1") (pin "3") (pinfunction "D+_3") (pintype "bidirectional"))
    )
    (net (code "104") (name "unconnected-(U$1-D--Pad2)") (class "Default")
      (node (ref "U$1") (pin "2") (pinfunction "D-_2") (pintype "bidirectional"))
    )
    (net (code "105") (name "unconnected-(U$1-ID-Pad4)") (class "Default")
      (node (ref "U$1") (pin "4") (pinfunction "ID_4") (pintype "bidirectional"))
    )
    (net (code "106") (name "unconnected-(U$2-PadCD)") (class "Default")
      (node (ref "U$2") (pin "CD") (pinfunction "CD_CD") (pintype "bidirectional"))
    )
    (net (code "107") (name "unconnected-(U1-GPB5-Pad6)") (class "Default")
      (node (ref "U1") (pin "6") (pinfunction "GPB5_6") (pintype "bidirectional"))
    )
    (net (code "108") (name "unconnected-(U1-GPB6-Pad7)") (class "Default")
      (node (ref "U1") (pin "7") (pinfunction "GPB6_7") (pintype "bidirectional"))
    )
    (net (code "109") (name "unconnected-(U1-INTA-Pad20)") (class "Default")
      (node (ref "U1") (pin "20") (pinfunction "INTA_20") (pintype "output"))
    )
    (net (code "110") (name "unconnected-(U1-INTB-Pad19)") (class "Default")
      (node (ref "U1") (pin "19") (pinfunction "INTB_19") (pintype "output"))
    )
    (net (code "111") (name "unconnected-(U1-NC-Pad11)") (class "Default")
      (node (ref "U1") (pin "11") (pinfunction "NC_11") (pintype "no_connect"))
    )
    (net (code "112") (name "unconnected-(U1-NC_2-Pad14)") (class "Default")
      (node (ref "U1") (pin "14") (pinfunction "NC_2_14") (pintype "no_connect"))
    )
    (net (code "113") (name "unconnected-(U2-AIN1-Pad5)") (class "Default")
      (node (ref "U2") (pin "5") (pinfunction "AIN1_5") (pintype "bidirectional"))
    )
    (net (code "114") (name "unconnected-(U2-AIN2-Pad6)") (class "Default")
      (node (ref "U2") (pin "6") (pinfunction "AIN2_6") (pintype "bidirectional"))
    )
    (net (code "115") (name "unconnected-(U2-AIN3-Pad7)") (class "Default")
      (node (ref "U2") (pin "7") (pinfunction "AIN3_7") (pintype "bidirectional"))
    )
    (net (code "116") (name "unconnected-(U3-INTA-Pad20)") (class "Default")
      (node (ref "U3") (pin "20") (pinfunction "INTA_20") (pintype "output"))
    )
    (net (code "117") (name "unconnected-(U3-INTB-Pad19)") (class "Default")
      (node (ref "U3") (pin "19") (pinfunction "INTB_19") (pintype "output"))
    )
    (net (code "118") (name "unconnected-(U3-NC-Pad11)") (class "Default")
      (node (ref "U3") (pin "11") (pinfunction "NC_11") (pintype "no_connect"))
    )
    (net (code "119") (name "unconnected-(U3-NC_2-Pad14)") (class "Default")
      (node (ref "U3") (pin "14") (pinfunction "NC_2_14") (pintype "no_connect"))
    )
    (net (code "120") (name "unconnected-(U4-A3-Pad4)") (class "Default")
      (node (ref "U4") (pin "4") (pinfunction "A3_4") (pintype "bidirectional"))
    )
    (net (code "121") (name "unconnected-(U4-A4-Pad5)") (class "Default")
      (node (ref "U4") (pin "5") (pinfunction "A4_5") (pintype "bidirectional"))
    )
    (net (code "122") (name "unconnected-(U4-A5-Pad6)") (class "Default")
      (node (ref "U4") (pin "6") (pinfunction "A5_6") (pintype "bidirectional"))
    )
    (net (code "123") (name "unconnected-(U4-A6-Pad7)") (class "Default")
      (node (ref "U4") (pin "7") (pinfunction "A6_7") (pintype "bidirectional"))
    )
    (net (code "124") (name "unconnected-(U4-A7-Pad8)") (class "Default")
      (node (ref "U4") (pin "8") (pinfunction "A7_8") (pintype "bidirectional"))
    )
    (net (code "125") (name "unconnected-(U4-A8-Pad9)") (class "Default")
      (node (ref "U4") (pin "9") (pinfunction "A8_9") (pintype "bidirectional"))
    )
    (net (code "126") (name "unconnected-(U4-B3-Pad17)") (class "Default")
      (node (ref "U4") (pin "17") (pinfunction "B3_17") (pintype "bidirectional"))
    )
    (net (code "127") (name "unconnected-(U4-B4-Pad16)") (class "Default")
      (node (ref "U4") (pin "16") (pinfunction "B4_16") (pintype "bidirectional"))
    )
    (net (code "128") (name "unconnected-(U4-B5-Pad15)") (class "Default")
      (node (ref "U4") (pin "15") (pinfunction "B5_15") (pintype "bidirectional"))
    )
    (net (code "129") (name "unconnected-(U4-B6-Pad14)") (class "Default")
      (node (ref "U4") (pin "14") (pinfunction "B6_14") (pintype "bidirectional"))
    )
    (net (code "130") (name "unconnected-(U4-B7-Pad13)") (class "Default")
      (node (ref "U4") (pin "13") (pinfunction "B7_13") (pintype "bidirectional"))
    )
    (net (code "131") (name "unconnected-(U4-B8-Pad12)") (class "Default")
      (node (ref "U4") (pin "12") (pinfunction "B8_12") (pintype "bidirectional"))
    )
  )
)
